# Sheet1.net
KiCad netlist of a schematic drawn in Altium Designer
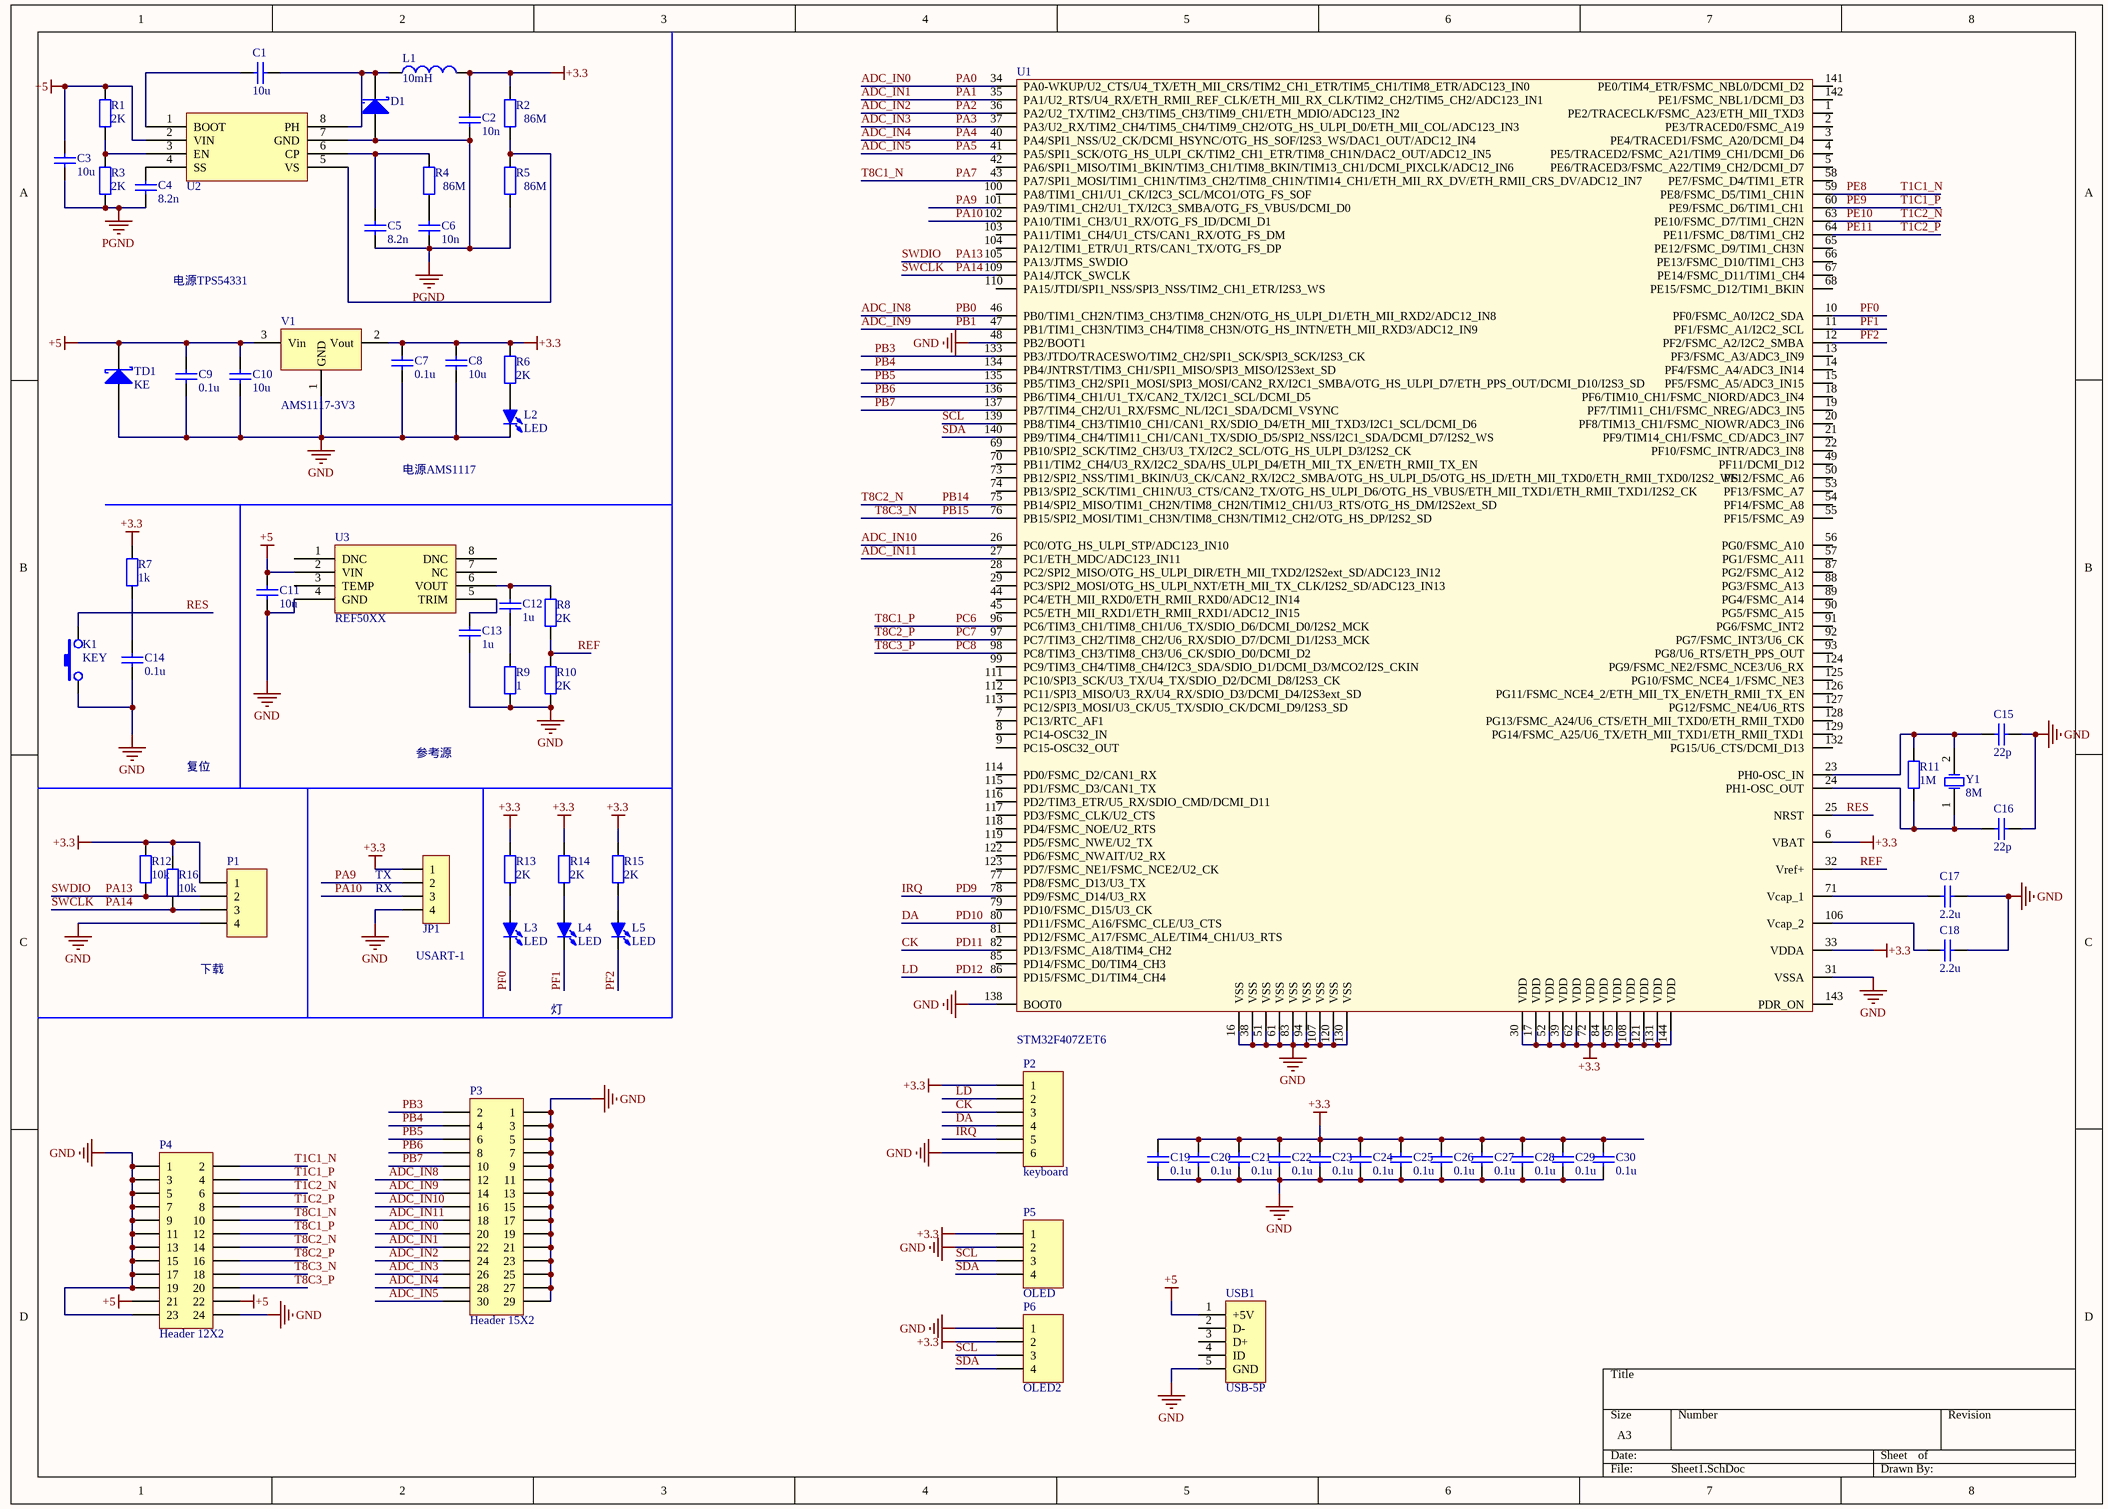
[diagram p0: Sheet1.SchDoc]

(export (version "E")
  (design (tool "Eeschema 10.0.6"))
  (components
    (comp (ref "C1")
      (value "10u")
      (footprint "Miscellaneous Devices:6-0805_N")
      (description "Capacitor")
      (fields (field (name "PUBLISHER") "Altium Limited"))
      (libsource (lib "Miscellaneous Devices") (part "Cap"))
    )
    (comp (ref "C2")
      (value "10n")
      (footprint "Miscellaneous Devices:6-0805_N")
      (description "Capacitor")
      (fields (field (name "PUBLISHER") "Altium Limited"))
      (libsource (lib "Miscellaneous Devices") (part "Cap"))
    )
    (comp (ref "C3")
      (value "10u")
      (footprint "Miscellaneous Devices:6-0805_N")
      (description "Capacitor")
      (fields (field (name "PUBLISHER") "Altium Limited"))
      (libsource (lib "Miscellaneous Devices") (part "Cap"))
    )
    (comp (ref "C4")
      (value "8.2n")
      (footprint "Miscellaneous Devices:6-0805_N")
      (description "Capacitor")
      (fields (field (name "PUBLISHER") "Altium Limited"))
      (libsource (lib "Miscellaneous Devices") (part "Cap"))
    )
    (comp (ref "C5")
      (value "8.2n")
      (footprint "Miscellaneous Devices:6-0805_N")
      (description "Capacitor")
      (fields (field (name "PUBLISHER") "Altium Limited"))
      (libsource (lib "Miscellaneous Devices") (part "Cap"))
    )
    (comp (ref "C6")
      (value "10n")
      (footprint "Miscellaneous Devices:6-0805_N")
      (description "Capacitor")
      (fields (field (name "PUBLISHER") "Altium Limited"))
      (libsource (lib "Miscellaneous Devices") (part "Cap"))
    )
    (comp (ref "C7")
      (value "0.1u")
      (footprint "04 - 电容:C 0603_L")
      (description "Capacitor")
      (fields (field (name "PUBLISHER") "Altium Limited"))
      (libsource (lib "Miscellaneous Devices") (part "Cap"))
    )
    (comp (ref "C8")
      (value "10u")
      (footprint "04 - 电容:C 0805_L")
      (description "Capacitor")
      (fields (field (name "PUBLISHER") "Altium Limited"))
      (libsource (lib "Miscellaneous Devices") (part "Cap"))
    )
    (comp (ref "C9")
      (value "0.1u")
      (footprint "04 - 电容:C 0805_L")
      (description "Capacitor")
      (fields (field (name "PUBLISHER") "Altium Limited"))
      (libsource (lib "Miscellaneous Devices") (part "Cap"))
    )
    (comp (ref "C10")
      (value "10u")
      (footprint "04 - 电容:C 0603_L")
      (description "Capacitor")
      (fields (field (name "PUBLISHER") "Altium Limited"))
      (libsource (lib "Miscellaneous Devices") (part "Cap"))
    )
    (comp (ref "C11")
      (value "10u")
      (footprint "04 - 电容:C 0603_L")
      (description "Capacitor")
      (fields (field (name "PUBLISHER") "Altium Limited"))
      (libsource (lib "Miscellaneous Devices") (part "Cap"))
    )
    (comp (ref "C12")
      (value "1u")
      (footprint "04 - 电容:C 0603_L")
      (description "Capacitor")
      (fields (field (name "PUBLISHER") "Altium Limited"))
      (libsource (lib "Miscellaneous Devices") (part "Cap"))
    )
    (comp (ref "C13")
      (value "1u")
      (footprint "04 - 电容:C 0603_L")
      (description "Capacitor")
      (fields (field (name "PUBLISHER") "Altium Limited"))
      (libsource (lib "Miscellaneous Devices") (part "Cap"))
    )
    (comp (ref "C14")
      (value "0.1u")
      (footprint "04 - 电容:C 0603_L")
      (description "Capacitor")
      (fields (field (name "PUBLISHER") "Altium Limited"))
      (libsource (lib "Miscellaneous Devices") (part "Cap"))
    )
    (comp (ref "C15")
      (value "22p")
      (footprint "04 - 电容:C 0603_L")
      (description "Capacitor")
      (fields (field (name "PUBLISHER") "Altium Limited"))
      (libsource (lib "Miscellaneous Devices") (part "Cap"))
    )
    (comp (ref "C16")
      (value "22p")
      (footprint "04 - 电容:C 0603_L")
      (description "Capacitor")
      (fields (field (name "PUBLISHER") "Altium Limited"))
      (libsource (lib "Miscellaneous Devices") (part "Cap"))
    )
    (comp (ref "C17")
      (value "2.2u")
      (footprint "04 - 电容:C 0805_M")
      (description "Capacitor")
      (fields (field (name "PUBLISHER") "Altium Limited"))
      (libsource (lib "Miscellaneous Devices") (part "Cap"))
    )
    (comp (ref "C18")
      (value "2.2u")
      (footprint "04 - 电容:C 0805_M")
      (description "Capacitor")
      (fields (field (name "PUBLISHER") "Altium Limited"))
      (libsource (lib "Miscellaneous Devices") (part "Cap"))
    )
    (comp (ref "C19")
      (value "0.1u")
      (footprint "04 - 电容:C 0603_L")
      (description "Capacitor")
      (fields (field (name "PUBLISHER") "Altium Limited"))
      (libsource (lib "Miscellaneous Devices") (part "Cap"))
    )
    (comp (ref "C20")
      (value "0.1u")
      (footprint "04 - 电容:C 0603_L")
      (description "Capacitor")
      (fields (field (name "PUBLISHER") "Altium Limited"))
      (libsource (lib "Miscellaneous Devices") (part "Cap"))
    )
    (comp (ref "C21")
      (value "0.1u")
      (footprint "04 - 电容:C 0603_L")
      (description "Capacitor")
      (fields (field (name "PUBLISHER") "Altium Limited"))
      (libsource (lib "Miscellaneous Devices") (part "Cap"))
    )
    (comp (ref "C22")
      (value "0.1u")
      (footprint "04 - 电容:C 0603_L")
      (description "Capacitor")
      (fields (field (name "PUBLISHER") "Altium Limited"))
      (libsource (lib "Miscellaneous Devices") (part "Cap"))
    )
    (comp (ref "C23")
      (value "0.1u")
      (footprint "04 - 电容:C 0603_L")
      (description "Capacitor")
      (fields (field (name "PUBLISHER") "Altium Limited"))
      (libsource (lib "Miscellaneous Devices") (part "Cap"))
    )
    (comp (ref "C24")
      (value "0.1u")
      (footprint "04 - 电容:C 0603_L")
      (description "Capacitor")
      (fields (field (name "PUBLISHER") "Altium Limited"))
      (libsource (lib "Miscellaneous Devices") (part "Cap"))
    )
    (comp (ref "C25")
      (value "0.1u")
      (footprint "04 - 电容:C 0603_L")
      (description "Capacitor")
      (fields (field (name "PUBLISHER") "Altium Limited"))
      (libsource (lib "Miscellaneous Devices") (part "Cap"))
    )
    (comp (ref "C26")
      (value "0.1u")
      (footprint "04 - 电容:C 0603_L")
      (description "Capacitor")
      (fields (field (name "PUBLISHER") "Altium Limited"))
      (libsource (lib "Miscellaneous Devices") (part "Cap"))
    )
    (comp (ref "C27")
      (value "0.1u")
      (footprint "04 - 电容:C 0603_L")
      (description "Capacitor")
      (fields (field (name "PUBLISHER") "Altium Limited"))
      (libsource (lib "Miscellaneous Devices") (part "Cap"))
    )
    (comp (ref "C28")
      (value "0.1u")
      (footprint "04 - 电容:C 0603_L")
      (description "Capacitor")
      (fields (field (name "PUBLISHER") "Altium Limited"))
      (libsource (lib "Miscellaneous Devices") (part "Cap"))
    )
    (comp (ref "C29")
      (value "0.1u")
      (footprint "04 - 电容:C 0603_L")
      (description "Capacitor")
      (fields (field (name "PUBLISHER") "Altium Limited"))
      (libsource (lib "Miscellaneous Devices") (part "Cap"))
    )
    (comp (ref "C30")
      (value "0.1u")
      (footprint "04 - 电容:C 0603_L")
      (description "Capacitor")
      (fields (field (name "PUBLISHER") "Altium Limited"))
      (libsource (lib "Miscellaneous Devices") (part "Cap"))
    )
    (comp (ref "D1")
      (value "D Schottky")
      (footprint "General:SMA")
      (description "Schottky Diode")
      (fields (field (name "PUBLISHER") "Altium Limited"))
      (libsource (lib "Miscellaneous Devices") (part "D Schottky"))
    )
    (comp (ref "JP1")
      (value "HDR-1X4")
      (footprint "XH2.54-WI-4P")
      (description "4P接插件")
      (libsource (lib "18 - 接插件-脚距2.54mm (100mil) ") (part "Header 4"))
    )
    (comp (ref "K1")
      (value "KEY")
      (footprint "KEY-6*6*6")
      (description "四角直插开关")
      (libsource (lib "03 - 按键-开关-晶振-蜂鸣器") (part "KEY"))
    )
    (comp (ref "L1")
      (value "10mH")
      (footprint "05 - 电感:SWPA4030S")
      (description "Inductor")
      (fields (field (name "PUBLISHER") "Altium Limited"))
      (libsource (lib "Miscellaneous Devices") (part "Inductor"))
    )
    (comp (ref "L2")
      (value "LED")
      (footprint "08 - LED发光二极管:LED 0805G")
      (description "发光二极管")
      (libsource (lib "02 - 二极管(LED)-三极管-整流桥") (part "LED"))
    )
    (comp (ref "L3")
      (value "LED")
      (footprint "08 - LED发光二极管:LED 0805G")
      (description "发光二极管")
      (libsource (lib "02 - 二极管(LED)-三极管-整流桥") (part "LED"))
    )
    (comp (ref "L4")
      (value "LED")
      (footprint "08 - LED发光二极管:LED 0805G")
      (description "发光二极管")
      (libsource (lib "02 - 二极管(LED)-三极管-整流桥") (part "LED"))
    )
    (comp (ref "L5")
      (value "LED")
      (footprint "08 - LED发光二极管:LED 0805G")
      (description "发光二极管")
      (libsource (lib "02 - 二极管(LED)-三极管-整流桥") (part "LED"))
    )
    (comp (ref "P1")
      (value "下载")
      (footprint "66 - XH2.54插座:XH2.54-WI-4P")
      (description "Header, 4-Pin")
      (fields (field (name "PUBLISHER") "Altium Limited"))
      (libsource (lib "Miscellaneous Connectors") (part "Header 4"))
    )
    (comp (ref "P2")
      (value "keyboard")
      (footprint "66 - XH2.54插座:XH2.54-WI-6P")
      (description "Header, 6-Pin")
      (fields (field (name "PUBLISHER") "Altium Limited"))
      (libsource (lib "Miscellaneous Connectors") (part "Header 6"))
    )
    (comp (ref "P3")
      (value "Header 15X2")
      (footprint "62 - 排针-排母:HDR2.54-WI-2x15P")
      (description "Header, 15-Pin, Dual row")
      (fields (field (name "PUBLISHER") "Altium Limited"))
      (libsource (lib "Miscellaneous Connectors") (part "Header 15X2"))
    )
    (comp (ref "P4")
      (value "Header 12X2")
      (footprint "62 - 排针-排母:HDR2.54-WI-2x12P")
      (description "Header, 12-Pin, Dual row")
      (fields (field (name "PUBLISHER") "Altium Limited"))
      (libsource (lib "Miscellaneous Connectors") (part "Header 12X2"))
    )
    (comp (ref "P5")
      (value "OLED")
      (footprint "62 - 排针-排母:HDR2.54-M-LI-4P")
      (description "Header, 4-Pin")
      (fields (field (name "PUBLISHER") "Altium Limited"))
      (libsource (lib "Miscellaneous Connectors") (part "Header 4"))
    )
    (comp (ref "P6")
      (value "OLED2")
      (footprint "62 - 排针-排母:HDR2.54-M-LI-4P")
      (description "Header, 4-Pin")
      (fields (field (name "PUBLISHER") "Altium Limited"))
      (libsource (lib "Miscellaneous Connectors") (part "Header 4"))
    )
    (comp (ref "R1")
      (value "2K")
      (footprint "01 - 电阻:R 0603_L")
      (description "Resistor")
      (fields (field (name "PUBLISHER") "Altium Limited"))
      (libsource (lib "Miscellaneous Devices") (part "Res2"))
    )
    (comp (ref "R2")
      (value "86M")
      (footprint "01 - 电阻:R 0603_L")
      (description "Resistor")
      (fields (field (name "PUBLISHER") "Altium Limited"))
      (libsource (lib "Miscellaneous Devices") (part "Res2"))
    )
    (comp (ref "R3")
      (value "2K")
      (footprint "01 - 电阻:R 0603_L")
      (description "Resistor")
      (fields (field (name "PUBLISHER") "Altium Limited"))
      (libsource (lib "Miscellaneous Devices") (part "Res2"))
    )
    (comp (ref "R4")
      (value "86M")
      (footprint "01 - 电阻:R 0603_L")
      (description "Resistor")
      (fields (field (name "PUBLISHER") "Altium Limited"))
      (libsource (lib "Miscellaneous Devices") (part "Res2"))
    )
    (comp (ref "R5")
      (value "86M")
      (footprint "01 - 电阻:R 0603_L")
      (description "Resistor")
      (fields (field (name "PUBLISHER") "Altium Limited"))
      (libsource (lib "Miscellaneous Devices") (part "Res2"))
    )
    (comp (ref "R6")
      (value "2K")
      (footprint "01 - 电阻:R 0603_L")
      (description "Resistor")
      (fields (field (name "PUBLISHER") "Altium Limited"))
      (libsource (lib "Miscellaneous Devices") (part "Res2"))
    )
    (comp (ref "R7")
      (value "1k")
      (footprint "01 - 电阻:R 0603_L")
      (description "Resistor")
      (fields (field (name "PUBLISHER") "Altium Limited"))
      (libsource (lib "Miscellaneous Devices") (part "Res2"))
    )
    (comp (ref "R8")
      (value "2K")
      (footprint "01 - 电阻:R 0603_L")
      (description "Resistor")
      (fields (field (name "PUBLISHER") "Altium Limited"))
      (libsource (lib "Miscellaneous Devices") (part "Res2"))
    )
    (comp (ref "R9")
      (value "1")
      (footprint "01 - 电阻:R 0603_L")
      (description "Resistor")
      (fields (field (name "PUBLISHER") "Altium Limited"))
      (libsource (lib "Miscellaneous Devices") (part "Res2"))
    )
    (comp (ref "R10")
      (value "2K")
      (footprint "01 - 电阻:R 0603_L")
      (description "Resistor")
      (fields (field (name "PUBLISHER") "Altium Limited"))
      (libsource (lib "Miscellaneous Devices") (part "Res2"))
    )
    (comp (ref "R11")
      (value "1M")
      (footprint "01 - 电阻:R 0603_L")
      (description "Resistor")
      (fields (field (name "PUBLISHER") "Altium Limited"))
      (libsource (lib "Miscellaneous Devices") (part "Res2"))
    )
    (comp (ref "R12")
      (value "10k")
      (footprint "01 - 电阻:R 0603_L")
      (description "Resistor")
      (fields (field (name "PUBLISHER") "Altium Limited"))
      (libsource (lib "Miscellaneous Devices") (part "Res2"))
    )
    (comp (ref "R13")
      (value "2K")
      (footprint "01 - 电阻:R 0603_L")
      (description "Resistor")
      (fields (field (name "PUBLISHER") "Altium Limited"))
      (libsource (lib "Miscellaneous Devices") (part "Res2"))
    )
    (comp (ref "R14")
      (value "2K")
      (footprint "01 - 电阻:R 0603_L")
      (description "Resistor")
      (fields (field (name "PUBLISHER") "Altium Limited"))
      (libsource (lib "Miscellaneous Devices") (part "Res2"))
    )
    (comp (ref "R15")
      (value "2K")
      (footprint "01 - 电阻:R 0603_L")
      (description "Resistor")
      (fields (field (name "PUBLISHER") "Altium Limited"))
      (libsource (lib "Miscellaneous Devices") (part "Res2"))
    )
    (comp (ref "R16")
      (value "10k")
      (footprint "01 - 电阻:R 0603_L")
      (description "Resistor")
      (fields (field (name "PUBLISHER") "Altium Limited"))
      (libsource (lib "Miscellaneous Devices") (part "Res2"))
    )
    (comp (ref "TD1")
      (value "KE")
      (footprint "07 - 二极管-整流桥堆:SMB")
      (description "Schottky Diode")
      (fields (field (name "PUBLISHER") "Altium Limited"))
      (libsource (lib "Miscellaneous Devices") (part "D Schottky"))
    )
    (comp (ref "U1")
      (value "STM32F407ZET6")
      (footprint "LQFP144")
      (libsource (lib "Explorer STM32F407封装库") (part "STM32F407ZET6"))
    )
    (comp (ref "U2")
      (value "TPS54331")
      (footprint "my:tps5450")
      (description "28V输入 3A")
      (libsource (lib "my") (part "TPS54331"))
    )
    (comp (ref "U3")
      (value "REF50XX")
      (footprint "11 - SO封装:SO-8")
      (description "基准源")
      (libsource (lib "my") (part "REF50XX"))
    )
    (comp (ref "USB1")
      (value "USB-5P")
      (footprint "48 - USB micro、3.1 Type C接口:USB-micro_A")
      (description "微型USB母座")
      (libsource (lib "04 - 接口类-USB接口-网口") (part "USB-5P"))
    )
    (comp (ref "V1")
      (value "AMS1117-3V3")
      (footprint "SOT223_N")
      (description "三端稳压芯片")
      (libsource (lib "08 - 稳压芯片-电源管理芯片") (part "AMS1117"))
    )
    (comp (ref "Y1")
      (value "8M")
      (footprint "09 - 晶振-晶体:OSC HC-49SMD")
      (description "Crystal Oscillator")
      (fields (field (name "PUBLISHER") "Altium Limited"))
      (libsource (lib "Miscellaneous Devices") (part "XTAL"))
    )
  )
  (nets
    (net (code "1") (name "+3.3") (class "Default")
      (node (ref "C19") (pin "2") (pinfunction "2_2") (pintype "passive"))
      (node (ref "C2") (pin "1") (pinfunction "1_1") (pintype "passive"))
      (node (ref "C20") (pin "2") (pinfunction "2_2") (pintype "passive"))
      (node (ref "C21") (pin "2") (pinfunction "2_2") (pintype "passive"))
      (node (ref "C22") (pin "2") (pinfunction "2_2") (pintype "passive"))
      (node (ref "C23") (pin "2") (pinfunction "2_2") (pintype "passive"))
      (node (ref "C24") (pin "2") (pinfunction "2_2") (pintype "passive"))
      (node (ref "C25") (pin "2") (pinfunction "2_2") (pintype "passive"))
      (node (ref "C26") (pin "2") (pinfunction "2_2") (pintype "passive"))
      (node (ref "C27") (pin "2") (pinfunction "2_2") (pintype "passive"))
      (node (ref "C28") (pin "2") (pinfunction "2_2") (pintype "passive"))
      (node (ref "C29") (pin "2") (pinfunction "2_2") (pintype "passive"))
      (node (ref "C30") (pin "2") (pinfunction "2_2") (pintype "passive"))
      (node (ref "C7") (pin "2") (pinfunction "2_2") (pintype "passive"))
      (node (ref "C8") (pin "2") (pinfunction "2_2") (pintype "passive"))
      (node (ref "JP1") (pin "1") (pinfunction "1_1") (pintype "passive"))
      (node (ref "L1") (pin "2") (pinfunction "2_2") (pintype "passive"))
      (node (ref "P1") (pin "1") (pinfunction "1_1") (pintype "passive"))
      (node (ref "P2") (pin "1") (pinfunction "1_1") (pintype "passive"))
      (node (ref "P5") (pin "1") (pinfunction "1_1") (pintype "passive"))
      (node (ref "P6") (pin "2") (pinfunction "2_2") (pintype "passive"))
      (node (ref "R12") (pin "2") (pinfunction "2_2") (pintype "passive"))
      (node (ref "R13") (pin "2") (pinfunction "2_2") (pintype "passive"))
      (node (ref "R14") (pin "2") (pinfunction "2_2") (pintype "passive"))
      (node (ref "R15") (pin "2") (pinfunction "2_2") (pintype "passive"))
      (node (ref "R16") (pin "2") (pinfunction "2_2") (pintype "passive"))
      (node (ref "R2") (pin "2") (pinfunction "2_2") (pintype "passive"))
      (node (ref "R6") (pin "2") (pinfunction "2_2") (pintype "passive"))
      (node (ref "R7") (pin "2") (pinfunction "2_2") (pintype "passive"))
      (node (ref "U1") (pin "108") (pinfunction "VDD_108") (pintype "passive"))
      (node (ref "U1") (pin "121") (pinfunction "VDD_121") (pintype "passive"))
      (node (ref "U1") (pin "131") (pinfunction "VDD_131") (pintype "passive"))
      (node (ref "U1") (pin "144") (pinfunction "VDD_144") (pintype "passive"))
      (node (ref "U1") (pin "17") (pinfunction "VDD_17") (pintype "passive"))
      (node (ref "U1") (pin "30") (pinfunction "VDD_30") (pintype "passive"))
      (node (ref "U1") (pin "33") (pinfunction "VDDA_33") (pintype "passive"))
      (node (ref "U1") (pin "39") (pinfunction "VDD_39") (pintype "passive"))
      (node (ref "U1") (pin "52") (pinfunction "VDD_52") (pintype "passive"))
      (node (ref "U1") (pin "6") (pinfunction "VBAT_6") (pintype "passive"))
      (node (ref "U1") (pin "62") (pinfunction "VDD_62") (pintype "passive"))
      (node (ref "U1") (pin "72") (pinfunction "VDD_72") (pintype "passive"))
      (node (ref "U1") (pin "84") (pinfunction "VDD_84") (pintype "passive"))
      (node (ref "U1") (pin "95") (pinfunction "VDD_95") (pintype "passive"))
      (node (ref "V1") (pin "2") (pinfunction "Vout_2") (pintype "passive"))
    )
    (net (code "2") (name "+5") (class "Default")
      (node (ref "C10") (pin "2") (pinfunction "2_2") (pintype "passive"))
      (node (ref "C11") (pin "2") (pinfunction "2_2") (pintype "passive"))
      (node (ref "C3") (pin "1") (pinfunction "1_1") (pintype "passive"))
      (node (ref "C9") (pin "2") (pinfunction "2_2") (pintype "passive"))
      (node (ref "P4") (pin "21") (pinfunction "21_21") (pintype "passive"))
      (node (ref "P4") (pin "22") (pinfunction "22_22") (pintype "passive"))
      (node (ref "R1") (pin "2") (pinfunction "2_2") (pintype "passive"))
      (node (ref "TD1") (pin "2") (pinfunction "K_2") (pintype "passive"))
      (node (ref "U2") (pin "2") (pinfunction "VIN_2") (pintype "passive"))
      (node (ref "U3") (pin "2") (pinfunction "VIN_2") (pintype "passive"))
      (node (ref "USB1") (pin "1") (pinfunction "+5V_1") (pintype "passive"))
      (node (ref "V1") (pin "3") (pinfunction "Vin_3") (pintype "passive"))
    )
    (net (code "3") (name "/ADC_IN0") (class "Default")
      (node (ref "P3") (pin "20") (pinfunction "20_20") (pintype "passive"))
      (node (ref "U1") (pin "34") (pinfunction "PA0-WKUP/U2_CTS/U4_TX/ETH_MII_CRS/TIM2_CH1_ETR/TIM5_CH1/TIM8_ETR/ADC123_IN0_34") (pintype "passive"))
    )
    (net (code "4") (name "/ADC_IN1") (class "Default")
      (node (ref "P3") (pin "22") (pinfunction "22_22") (pintype "passive"))
      (node (ref "U1") (pin "35") (pinfunction "PA1/U2_RTS/U4_RX/ETH_RMII_REF_CLK/ETH_MII_RX_CLK/TIM2_CH2/TIM5_CH2/ADC123_IN1_35") (pintype "passive"))
    )
    (net (code "5") (name "/ADC_IN2") (class "Default")
      (node (ref "P3") (pin "24") (pinfunction "24_24") (pintype "passive"))
      (node (ref "U1") (pin "36") (pinfunction "PA2/U2_TX/TIM2_CH3/TIM5_CH3/TIM9_CH1/ETH_MDIO/ADC123_IN2_36") (pintype "passive"))
    )
    (net (code "6") (name "/ADC_IN3") (class "Default")
      (node (ref "P3") (pin "26") (pinfunction "26_26") (pintype "passive"))
      (node (ref "U1") (pin "37") (pinfunction "PA3/U2_RX/TIM2_CH4/TIM5_CH4/TIM9_CH2/OTG_HS_ULPI_D0/ETH_MII_COL/ADC123_IN3_37") (pintype "passive"))
    )
    (net (code "7") (name "/ADC_IN4") (class "Default")
      (node (ref "P3") (pin "28") (pinfunction "28_28") (pintype "passive"))
      (node (ref "U1") (pin "40") (pinfunction "PA4/SPI1_NSS/U2_CK/DCMI_HSYNC/OTG_HS_SOF/I2S3_WS/DAC1_OUT/ADC12_IN4_40") (pintype "passive"))
    )
    (net (code "8") (name "/ADC_IN5") (class "Default")
      (node (ref "P3") (pin "30") (pinfunction "30_30") (pintype "passive"))
      (node (ref "U1") (pin "41") (pinfunction "PA5/SPI1_SCK/OTG_HS_ULPI_CK/TIM2_CH1_ETR/TIM8_CH1N/DAC2_OUT/ADC12_IN5_41") (pintype "passive"))
    )
    (net (code "9") (name "/ADC_IN8") (class "Default")
      (node (ref "P3") (pin "12") (pinfunction "12_12") (pintype "passive"))
      (node (ref "U1") (pin "46") (pinfunction "PB0/TIM1_CH2N/TIM3_CH3/TIM8_CH2N/OTG_HS_ULPI_D1/ETH_MII_RXD2/ADC12_IN8_46") (pintype "passive"))
    )
    (net (code "10") (name "/ADC_IN9") (class "Default")
      (node (ref "P3") (pin "14") (pinfunction "14_14") (pintype "passive"))
      (node (ref "U1") (pin "47") (pinfunction "PB1/TIM1_CH3N/TIM3_CH4/TIM8_CH3N/OTG_HS_INTN/ETH_MII_RXD3/ADC12_IN9_47") (pintype "passive"))
    )
    (net (code "11") (name "/ADC_IN10") (class "Default")
      (node (ref "P3") (pin "16") (pinfunction "16_16") (pintype "passive"))
      (node (ref "U1") (pin "26") (pinfunction "PC0/OTG_HS_ULPI_STP/ADC123_IN10_26") (pintype "passive"))
    )
    (net (code "12") (name "/ADC_IN11") (class "Default")
      (node (ref "P3") (pin "18") (pinfunction "18_18") (pintype "passive"))
      (node (ref "U1") (pin "27") (pinfunction "PC1/ETH_MDC/ADC123_IN11_27") (pintype "passive"))
    )
    (net (code "13") (name "/CK") (class "Default")
      (node (ref "P2") (pin "3") (pinfunction "3_3") (pintype "passive"))
      (node (ref "U1") (pin "82") (pinfunction "PD13/FSMC_A18/TIM4_CH2_82") (pintype "passive"))
    )
    (net (code "14") (name "/DA") (class "Default")
      (node (ref "P2") (pin "4") (pinfunction "4_4") (pintype "passive"))
      (node (ref "U1") (pin "80") (pinfunction "PD11/FSMC_A16/FSMC_CLE/U3_CTS_80") (pintype "passive"))
    )
    (net (code "15") (name "/IRQ") (class "Default")
      (node (ref "P2") (pin "5") (pinfunction "5_5") (pintype "passive"))
      (node (ref "U1") (pin "78") (pinfunction "PD9/FSMC_D14/U3_RX_78") (pintype "passive"))
    )
    (net (code "16") (name "/LD") (class "Default")
      (node (ref "P2") (pin "2") (pinfunction "2_2") (pintype "passive"))
      (node (ref "U1") (pin "86") (pinfunction "PD15/FSMC_D1/TIM4_CH4_86") (pintype "passive"))
    )
    (net (code "17") (name "/PA7") (class "Default")
      (node (ref "P4") (pin "10") (pinfunction "10_10") (pintype "passive"))
      (node (ref "U1") (pin "43") (pinfunction "PA7/SPI1_MOSI/TIM1_CH1N/TIM3_CH2/TIM8_CH1N/TIM14_CH1/ETH_MII_RX_DV/ETH_RMII_CRS_DV/ADC12_IN7_43") (pintype "passive"))
    )
    (net (code "18") (name "/PA9") (class "Default")
      (node (ref "JP1") (pin "2") (pinfunction "2_2") (pintype "passive"))
      (node (ref "U1") (pin "101") (pinfunction "PA9/TIM1_CH2/U1_TX/I2C3_SMBA/OTG_FS_VBUS/DCMI_D0_101") (pintype "passive"))
    )
    (net (code "19") (name "/PA10") (class "Default")
      (node (ref "JP1") (pin "3") (pinfunction "3_3") (pintype "passive"))
      (node (ref "U1") (pin "102") (pinfunction "PA10/TIM1_CH3/U1_RX/OTG_FS_ID/DCMI_D1_102") (pintype "passive"))
    )
    (net (code "20") (name "/PA13") (class "Default")
      (node (ref "P1") (pin "2") (pinfunction "2_2") (pintype "passive"))
      (node (ref "R12") (pin "1") (pinfunction "1_1") (pintype "passive"))
      (node (ref "U1") (pin "105") (pinfunction "PA13/JTMS_SWDIO_105") (pintype "passive"))
    )
    (net (code "21") (name "/PA14") (class "Default")
      (node (ref "P1") (pin "3") (pinfunction "3_3") (pintype "passive"))
      (node (ref "R16") (pin "1") (pinfunction "1_1") (pintype "passive"))
      (node (ref "U1") (pin "109") (pinfunction "PA14/JTCK_SWCLK_109") (pintype "passive"))
    )
    (net (code "22") (name "/PB3") (class "Default")
      (node (ref "P3") (pin "2") (pinfunction "2_2") (pintype "passive"))
      (node (ref "U1") (pin "133") (pinfunction "PB3/JTDO/TRACESWO/TIM2_CH2/SPI1_SCK/SPI3_SCK/I2S3_CK_133") (pintype "passive"))
    )
    (net (code "23") (name "/PB4") (class "Default")
      (node (ref "P3") (pin "4") (pinfunction "4_4") (pintype "passive"))
      (node (ref "U1") (pin "134") (pinfunction "PB4/JNTRST/TIM3_CH1/SPI1_MISO/SPI3_MISO/I2S3ext_SD_134") (pintype "passive"))
    )
    (net (code "24") (name "/PB5") (class "Default")
      (node (ref "P3") (pin "6") (pinfunction "6_6") (pintype "passive"))
      (node (ref "U1") (pin "135") (pinfunction "PB5/TIM3_CH2/SPI1_MOSI/SPI3_MOSI/CAN2_RX/I2C1_SMBA/OTG_HS_ULPI_D7/ETH_PPS_OUT/DCMI_D10/I2S3_SD_135") (pintype "passive"))
    )
    (net (code "25") (name "/PB6") (class "Default")
      (node (ref "P3") (pin "8") (pinfunction "8_8") (pintype "passive"))
      (node (ref "U1") (pin "136") (pinfunction "PB6/TIM4_CH1/U1_TX/CAN2_TX/I2C1_SCL/DCMI_D5_136") (pintype "passive"))
    )
    (net (code "26") (name "/PB7") (class "Default")
      (node (ref "P3") (pin "10") (pinfunction "10_10") (pintype "passive"))
      (node (ref "U1") (pin "137") (pinfunction "PB7/TIM4_CH2/U1_RX/FSMC_NL/I2C1_SDA/DCMI_VSYNC_137") (pintype "passive"))
    )
    (net (code "27") (name "/PB14") (class "Default")
      (node (ref "P4") (pin "14") (pinfunction "14_14") (pintype "passive"))
      (node (ref "U1") (pin "75") (pinfunction "PB14/SPI2_MISO/TIM1_CH2N/TIM8_CH2N/TIM12_CH1/U3_RTS/OTG_HS_DM/I2S2ext_SD_75") (pintype "passive"))
    )
    (net (code "28") (name "/PB15") (class "Default")
      (node (ref "P4") (pin "18") (pinfunction "18_18") (pintype "passive"))
      (node (ref "U1") (pin "76") (pinfunction "PB15/SPI2_MOSI/TIM1_CH3N/TIM8_CH3N/TIM12_CH2/OTG_HS_DP/I2S2_SD_76") (pintype "passive"))
    )
    (net (code "29") (name "/PC6") (class "Default")
      (node (ref "P4") (pin "12") (pinfunction "12_12") (pintype "passive"))
      (node (ref "U1") (pin "96") (pinfunction "PC6/TIM3_CH1/TIM8_CH1/U6_TX/SDIO_D6/DCMI_D0/I2S2_MCK_96") (pintype "passive"))
    )
    (net (code "30") (name "/PC7") (class "Default")
      (node (ref "P4") (pin "16") (pinfunction "16_16") (pintype "passive"))
      (node (ref "U1") (pin "97") (pinfunction "PC7/TIM3_CH2/TIM8_CH2/U6_RX/SDIO_D7/DCMI_D1/I2S3_MCK_97") (pintype "passive"))
    )
    (net (code "31") (name "/PC8") (class "Default")
      (node (ref "P4") (pin "20") (pinfunction "20_20") (pintype "passive"))
      (node (ref "U1") (pin "98") (pinfunction "PC8/TIM3_CH3/TIM8_CH3/U6_CK/SDIO_D0/DCMI_D2_98") (pintype "passive"))
    )
    (net (code "32") (name "/PE8") (class "Default")
      (node (ref "P4") (pin "2") (pinfunction "2_2") (pintype "passive"))
      (node (ref "U1") (pin "59") (pinfunction "PE8/FSMC_D5/TIM1_CH1N_59") (pintype "passive"))
    )
    (net (code "33") (name "/PE9") (class "Default")
      (node (ref "P4") (pin "4") (pinfunction "4_4") (pintype "passive"))
      (node (ref "U1") (pin "60") (pinfunction "PE9/FSMC_D6/TIM1_CH1_60") (pintype "passive"))
    )
    (net (code "34") (name "/PE10") (class "Default")
      (node (ref "P4") (pin "6") (pinfunction "6_6") (pintype "passive"))
      (node (ref "U1") (pin "63") (pinfunction "PE10/FSMC_D7/TIM1_CH2N_63") (pintype "passive"))
    )
    (net (code "35") (name "/PE11") (class "Default")
      (node (ref "P4") (pin "8") (pinfunction "8_8") (pintype "passive"))
      (node (ref "U1") (pin "64") (pinfunction "PE11/FSMC_D8/TIM1_CH2_64") (pintype "passive"))
    )
    (net (code "36") (name "/PF0") (class "Default")
      (node (ref "L3") (pin "2") (pinfunction "K_2") (pintype "passive"))
      (node (ref "U1") (pin "10") (pinfunction "PF0/FSMC_A0/I2C2_SDA_10") (pintype "passive"))
    )
    (net (code "37") (name "/PF1") (class "Default")
      (node (ref "L4") (pin "2") (pinfunction "K_2") (pintype "passive"))
      (node (ref "U1") (pin "11") (pinfunction "PF1/FSMC_A1/I2C2_SCL_11") (pintype "passive"))
    )
    (net (code "38") (name "/PF2") (class "Default")
      (node (ref "L5") (pin "2") (pinfunction "K_2") (pintype "passive"))
      (node (ref "U1") (pin "12") (pinfunction "PF2/FSMC_A2/I2C2_SMBA_12") (pintype "passive"))
    )
    (net (code "39") (name "/REF") (class "Default")
      (node (ref "R10") (pin "2") (pinfunction "2_2") (pintype "passive"))
      (node (ref "R8") (pin "1") (pinfunction "1_1") (pintype "passive"))
      (node (ref "U1") (pin "32") (pinfunction "Vref+_32") (pintype "passive"))
    )
    (net (code "40") (name "/RES") (class "Default")
      (node (ref "K1") (pin "2") (pinfunction "2_2") (pintype "passive"))
      (node (ref "U1") (pin "25") (pinfunction "NRST_25") (pintype "passive"))
    )
    (net (code "41") (name "/SCL") (class "Default")
      (node (ref "P5") (pin "3") (pinfunction "3_3") (pintype "passive"))
      (node (ref "P6") (pin "3") (pinfunction "3_3") (pintype "passive"))
      (node (ref "U1") (pin "139") (pinfunction "PB8/TIM4_CH3/TIM10_CH1/CAN1_RX/SDIO_D4/ETH_MII_TXD3/I2C1_SCL/DCMI_D6_139") (pintype "passive"))
    )
    (net (code "42") (name "/SDA") (class "Default")
      (node (ref "P5") (pin "4") (pinfunction "4_4") (pintype "passive"))
      (node (ref "P6") (pin "4") (pinfunction "4_4") (pintype "passive"))
      (node (ref "U1") (pin "140") (pinfunction "PB9/TIM4_CH4/TIM11_CH1/CAN1_TX/SDIO_D5/SPI2_NSS/I2C1_SDA/DCMI_D7/I2S2_WS_140") (pintype "passive"))
    )
    (net (code "43") (name "GND") (class "Default")
      (node (ref "C10") (pin "1") (pinfunction "1_1") (pintype "passive"))
      (node (ref "C11") (pin "1") (pinfunction "1_1") (pintype "passive"))
      (node (ref "C13") (pin "1") (pinfunction "1_1") (pintype "passive"))
      (node (ref "C14") (pin "1") (pinfunction "1_1") (pintype "passive"))
      (node (ref "C15") (pin "2") (pinfunction "2_2") (pintype "passive"))
      (node (ref "C16") (pin "2") (pinfunction "2_2") (pintype "passive"))
      (node (ref "C17") (pin "2") (pinfunction "2_2") (pintype "passive"))
      (node (ref "C18") (pin "2") (pinfunction "2_2") (pintype "passive"))
      (node (ref "C19") (pin "1") (pinfunction "1_1") (pintype "passive"))
      (node (ref "C20") (pin "1") (pinfunction "1_1") (pintype "passive"))
      (node (ref "C21") (pin "1") (pinfunction "1_1") (pintype "passive"))
      (node (ref "C22") (pin "1") (pinfunction "1_1") (pintype "passive"))
      (node (ref "C23") (pin "1") (pinfunction "1_1") (pintype "passive"))
      (node (ref "C24") (pin "1") (pinfunction "1_1") (pintype "passive"))
      (node (ref "C25") (pin "1") (pinfunction "1_1") (pintype "passive"))
      (node (ref "C26") (pin "1") (pinfunction "1_1") (pintype "passive"))
      (node (ref "C27") (pin "1") (pinfunction "1_1") (pintype "passive"))
      (node (ref "C28") (pin "1") (pinfunction "1_1") (pintype "passive"))
      (node (ref "C29") (pin "1") (pinfunction "1_1") (pintype "passive"))
      (node (ref "C30") (pin "1") (pinfunction "1_1") (pintype "passive"))
      (node (ref "C7") (pin "1") (pinfunction "1_1") (pintype "passive"))
      (node (ref "C8") (pin "1") (pinfunction "1_1") (pintype "passive"))
      (node (ref "C9") (pin "1") (pinfunction "1_1") (pintype "passive"))
      (node (ref "JP1") (pin "4") (pinfunction "4_4") (pintype "passive"))
      (node (ref "K1") (pin "1") (pinfunction "1_1") (pintype "passive"))
      (node (ref "L2") (pin "2") (pinfunction "K_2") (pintype "passive"))
      (node (ref "P1") (pin "4") (pinfunction "4_4") (pintype "passive"))
      (node (ref "P2") (pin "6") (pinfunction "6_6") (pintype "passive"))
      (node (ref "P3") (pin "1") (pinfunction "1_1") (pintype "passive"))
      (node (ref "P3") (pin "11") (pinfunction "11_11") (pintype "passive"))
      (node (ref "P3") (pin "13") (pinfunction "13_13") (pintype "passive"))
      (node (ref "P3") (pin "15") (pinfunction "15_15") (pintype "passive"))
      (node (ref "P3") (pin "17") (pinfunction "17_17") (pintype "passive"))
      (node (ref "P3") (pin "19") (pinfunction "19_19") (pintype "passive"))
      (node (ref "P3") (pin "21") (pinfunction "21_21") (pintype "passive"))
      (node (ref "P3") (pin "23") (pinfunction "23_23") (pintype "passive"))
      (node (ref "P3") (pin "25") (pinfunction "25_25") (pintype "passive"))
      (node (ref "P3") (pin "27") (pinfunction "27_27") (pintype "passive"))
      (node (ref "P3") (pin "29") (pinfunction "29_29") (pintype "passive"))
      (node (ref "P3") (pin "3") (pinfunction "3_3") (pintype "passive"))
      (node (ref "P3") (pin "5") (pinfunction "5_5") (pintype "passive"))
      (node (ref "P3") (pin "7") (pinfunction "7_7") (pintype "passive"))
      (node (ref "P3") (pin "9") (pinfunction "9_9") (pintype "passive"))
      (node (ref "P4") (pin "1") (pinfunction "1_1") (pintype "passive"))
      (node (ref "P4") (pin "11") (pinfunction "11_11") (pintype "passive"))
      (node (ref "P4") (pin "13") (pinfunction "13_13") (pintype "passive"))
      (node (ref "P4") (pin "15") (pinfunction "15_15") (pintype "passive"))
      (node (ref "P4") (pin "17") (pinfunction "17_17") (pintype "passive"))
      (node (ref "P4") (pin "19") (pinfunction "19_19") (pintype "passive"))
      (node (ref "P4") (pin "23") (pinfunction "23_23") (pintype "passive"))
      (node (ref "P4") (pin "24") (pinfunction "24_24") (pintype "passive"))
      (node (ref "P4") (pin "3") (pinfunction "3_3") (pintype "passive"))
      (node (ref "P4") (pin "5") (pinfunction "5_5") (pintype "passive"))
      (node (ref "P4") (pin "7") (pinfunction "7_7") (pintype "passive"))
      (node (ref "P4") (pin "9") (pinfunction "9_9") (pintype "passive"))
      (node (ref "P5") (pin "2") (pinfunction "2_2") (pintype "passive"))
      (node (ref "P6") (pin "1") (pinfunction "1_1") (pintype "passive"))
      (node (ref "R10") (pin "1") (pinfunction "1_1") (pintype "passive"))
      (node (ref "R9") (pin "1") (pinfunction "1_1") (pintype "passive"))
      (node (ref "TD1") (pin "1") (pinfunction "A_1") (pintype "passive"))
      (node (ref "U1") (pin "107") (pinfunction "VSS_107") (pintype "passive"))
      (node (ref "U1") (pin "120") (pinfunction "VSS_120") (pintype "passive"))
      (node (ref "U1") (pin "130") (pinfunction "VSS_130") (pintype "passive"))
      (node (ref "U1") (pin "138") (pinfunction "BOOT0_138") (pintype "passive"))
      (node (ref "U1") (pin "16") (pinfunction "VSS_16") (pintype "passive"))
      (node (ref "U1") (pin "31") (pinfunction "VSSA_31") (pintype "passive"))
      (node (ref "U1") (pin "38") (pinfunction "VSS_38") (pintype "passive"))
      (node (ref "U1") (pin "48") (pinfunction "PB2/BOOT1_48") (pintype "passive"))
      (node (ref "U1") (pin "51") (pinfunction "VSS_51") (pintype "passive"))
      (node (ref "U1") (pin "61") (pinfunction "VSS_61") (pintype "passive"))
      (node (ref "U1") (pin "83") (pinfunction "VSS_83") (pintype "passive"))
      (node (ref "U1") (pin "94") (pinfunction "VSS_94") (pintype "passive"))
      (node (ref "U3") (pin "4") (pinfunction "GND_4") (pintype "passive"))
      (node (ref "USB1") (pin "5") (pinfunction "GND_5") (pintype "passive"))
      (node (ref "V1") (pin "1") (pinfunction "GND_1") (pintype "passive"))
    )
    (net (code "44") (name "Net-(C6-Pad1)") (class "Default")
      (node (ref "C6") (pin "1") (pinfunction "1_1") (pintype "passive"))
      (node (ref "R4") (pin "1") (pinfunction "1_1") (pintype "passive"))
    )
    (net (code "45") (name "Net-(C12-Pad1)") (class "Default")
      (node (ref "C12") (pin "1") (pinfunction "1_1") (pintype "passive"))
      (node (ref "R9") (pin "2") (pinfunction "2_2") (pintype "passive"))
    )
    (net (code "46") (name "Net-(C14-Pad2)") (class "Default")
      (node (ref "C14") (pin "2") (pinfunction "2_2") (pintype "passive"))
      (node (ref "R7") (pin "1") (pinfunction "1_1") (pintype "passive"))
    )
    (net (code "47") (name "Net-(D1-K)") (class "Default")
      (node (ref "C1") (pin "1") (pinfunction "1_1") (pintype "passive"))
      (node (ref "D1") (pin "2") (pinfunction "K_2") (pintype "passive"))
      (node (ref "L1") (pin "1") (pinfunction "1_1") (pintype "passive"))
      (node (ref "U2") (pin "8") (pinfunction "PH_8") (pintype "passive"))
    )
    (net (code "48") (name "Net-(L2-A)") (class "Default")
      (node (ref "L2") (pin "1") (pinfunction "A_1") (pintype "passive"))
      (node (ref "R6") (pin "1") (pinfunction "1_1") (pintype "passive"))
    )
    (net (code "49") (name "Net-(L3-A)") (class "Default")
      (node (ref "L3") (pin "1") (pinfunction "A_1") (pintype "passive"))
      (node (ref "R13") (pin "1") (pinfunction "1_1") (pintype "passive"))
    )
    (net (code "50") (name "Net-(L4-A)") (class "Default")
      (node (ref "L4") (pin "1") (pinfunction "A_1") (pintype "passive"))
      (node (ref "R14") (pin "1") (pinfunction "1_1") (pintype "passive"))
    )
    (net (code "51") (name "Net-(L5-A)") (class "Default")
      (node (ref "L5") (pin "1") (pinfunction "A_1") (pintype "passive"))
      (node (ref "R15") (pin "1") (pinfunction "1_1") (pintype "passive"))
    )
    (net (code "52") (name "Net-(U1-PH0-OSC_IN)") (class "Default")
      (node (ref "C15") (pin "1") (pinfunction "1_1") (pintype "passive"))
      (node (ref "R11") (pin "2") (pinfunction "2_2") (pintype "passive"))
      (node (ref "U1") (pin "23") (pinfunction "PH0-OSC_IN_23") (pintype "passive"))
      (node (ref "Y1") (pin "2") (pinfunction "OSC2_2") (pintype "passive"))
    )
    (net (code "53") (name "Net-(U1-PH1-OSC_OUT)") (class "Default")
      (node (ref "C16") (pin "1") (pinfunction "1_1") (pintype "passive"))
      (node (ref "R11") (pin "1") (pinfunction "1_1") (pintype "passive"))
      (node (ref "U1") (pin "24") (pinfunction "PH1-OSC_OUT_24") (pintype "passive"))
      (node (ref "Y1") (pin "1") (pinfunction "OSC1_1") (pintype "passive"))
    )
    (net (code "54") (name "Net-(U1-Vcap_1)") (class "Default")
      (node (ref "C17") (pin "1") (pinfunction "1_1") (pintype "passive"))
      (node (ref "U1") (pin "71") (pinfunction "Vcap_1_71") (pintype "passive"))
    )
    (net (code "55") (name "Net-(U1-Vcap_2)") (class "Default")
      (node (ref "C18") (pin "1") (pinfunction "1_1") (pintype "passive"))
      (node (ref "U1") (pin "106") (pinfunction "Vcap_2_106") (pintype "passive"))
    )
    (net (code "56") (name "Net-(U2-BOOT)") (class "Default")
      (node (ref "C1") (pin "2") (pinfunction "2_2") (pintype "passive"))
      (node (ref "U2") (pin "1") (pinfunction "BOOT_1") (pintype "passive"))
    )
    (net (code "57") (name "Net-(U2-CP)") (class "Default")
      (node (ref "C5") (pin "1") (pinfunction "1_1") (pintype "passive"))
      (node (ref "R4") (pin "2") (pinfunction "2_2") (pintype "passive"))
      (node (ref "U2") (pin "6") (pinfunction "CP_6") (pintype "passive"))
    )
    (net (code "58") (name "Net-(U2-EN)") (class "Default")
      (node (ref "R1") (pin "1") (pinfunction "1_1") (pintype "passive"))
      (node (ref "R3") (pin "2") (pinfunction "2_2") (pintype "passive"))
      (node (ref "U2") (pin "3") (pinfunction "EN_3") (pintype "passive"))
    )
    (net (code "59") (name "Net-(U2-SS)") (class "Default")
      (node (ref "C4") (pin "1") (pinfunction "1_1") (pintype "passive"))
      (node (ref "U2") (pin "4") (pinfunction "SS_4") (pintype "passive"))
    )
    (net (code "60") (name "Net-(U2-VS)") (class "Default")
      (node (ref "R2") (pin "1") (pinfunction "1_1") (pintype "passive"))
      (node (ref "R5") (pin "2") (pinfunction "2_2") (pintype "passive"))
      (node (ref "U2") (pin "5") (pinfunction "VS_5") (pintype "passive"))
    )
    (net (code "61") (name "Net-(U3-TRIM)") (class "Default")
      (node (ref "C13") (pin "2") (pinfunction "2_2") (pintype "passive"))
      (node (ref "U3") (pin "5") (pinfunction "TRIM_5") (pintype "passive"))
    )
    (net (code "62") (name "Net-(U3-VOUT)") (class "Default")
      (node (ref "C12") (pin "2") (pinfunction "2_2") (pintype "passive"))
      (node (ref "R8") (pin "2") (pinfunction "2_2") (pintype "passive"))
      (node (ref "U3") (pin "6") (pinfunction "VOUT_6") (pintype "passive"))
    )
    (net (code "63") (name "PGND") (class "Default")
      (node (ref "C2") (pin "2") (pinfunction "2_2") (pintype "passive"))
      (node (ref "C3") (pin "2") (pinfunction "2_2") (pintype "passive"))
      (node (ref "C4") (pin "2") (pinfunction "2_2") (pintype "passive"))
      (node (ref "C5") (pin "2") (pinfunction "2_2") (pintype "passive"))
      (node (ref "C6") (pin "2") (pinfunction "2_2") (pintype "passive"))
      (node (ref "D1") (pin "1") (pinfunction "A_1") (pintype "passive"))
      (node (ref "R3") (pin "1") (pinfunction "1_1") (pintype "passive"))
      (node (ref "R5") (pin "1") (pinfunction "1_1") (pintype "passive"))
      (node (ref "U2") (pin "7") (pinfunction "GND_7") (pintype "passive"))
    )
    (net (code "64") (name "unconnected-(U1-PA6{slash}SPI1_MISO{slash}TIM1_BKIN{slash}TIM3_CH1{slash}TIM8_BKIN{slash}TIM13_CH1{slash}DCMI_PIXCLK{slash}ADC12_IN6-Pad42)") (class "Default")
      (node (ref "U1") (pin "42") (pinfunction "PA6/SPI1_MISO/TIM1_BKIN/TIM3_CH1/TIM8_BKIN/TIM13_CH1/DCMI_PIXCLK/ADC12_IN6_42") (pintype "passive"))
    )
    (net (code "65") (name "unconnected-(U1-PA8{slash}TIM1_CH1{slash}U1_CK{slash}I2C3_SCL{slash}MCO1{slash}OTG_FS_SOF-Pad100)") (class "Default")
      (node (ref "U1") (pin "100") (pinfunction "PA8/TIM1_CH1/U1_CK/I2C3_SCL/MCO1/OTG_FS_SOF_100") (pintype "passive"))
    )
    (net (code "66") (name "unconnected-(U1-PA11{slash}TIM1_CH4{slash}U1_CTS{slash}CAN1_RX{slash}OTG_FS_DM-Pad103)") (class "Default")
      (node (ref "U1") (pin "103") (pinfunction "PA11/TIM1_CH4/U1_CTS/CAN1_RX/OTG_FS_DM_103") (pintype "passive"))
    )
    (net (code "67") (name "unconnected-(U1-PA12{slash}TIM1_ETR{slash}U1_RTS{slash}CAN1_TX{slash}OTG_FS_DP-Pad104)") (class "Default")
      (node (ref "U1") (pin "104") (pinfunction "PA12/TIM1_ETR/U1_RTS/CAN1_TX/OTG_FS_DP_104") (pintype "passive"))
    )
    (net (code "68") (name "unconnected-(U1-PA15{slash}JTDI{slash}SPI1_NSS{slash}SPI3_NSS{slash}TIM2_CH1_ETR{slash}I2S3_WS-Pad110)") (class "Default")
      (node (ref "U1") (pin "110") (pinfunction "PA15/JTDI/SPI1_NSS/SPI3_NSS/TIM2_CH1_ETR/I2S3_WS_110") (pintype "passive"))
    )
    (net (code "69") (name "unconnected-(U1-PB10{slash}SPI2_SCK{slash}TIM2_CH3{slash}U3_TX{slash}I2C2_SCL{slash}OTG_HS_ULPI_D3{slash}I2S2_CK-Pad69)") (class "Default")
      (node (ref "U1") (pin "69") (pinfunction "PB10/SPI2_SCK/TIM2_CH3/U3_TX/I2C2_SCL/OTG_HS_ULPI_D3/I2S2_CK_69") (pintype "passive"))
    )
    (net (code "70") (name "unconnected-(U1-PB11{slash}TIM2_CH4{slash}U3_RX{slash}I2C2_SDA{slash}HS_ULPI_D4{slash}ETH_MII_TX_EN{slash}ETH_RMII_TX_EN-Pad70)") (class "Default")
      (node (ref "U1") (pin "70") (pinfunction "PB11/TIM2_CH4/U3_RX/I2C2_SDA/HS_ULPI_D4/ETH_MII_TX_EN/ETH_RMII_TX_EN_70") (pintype "passive"))
    )
    (net (code "71") (name "unconnected-(U1-PB12{slash}SPI2_NSS{slash}TIM1_BKIN{slash}U3_CK{slash}CAN2_RX{slash}I2C2_SMBA{slash}OTG_HS_ULPI_D5{slash}OTG_HS_ID{slash}ETH_MII_TXD0{slash}ETH_RMII_TXD0{slash}I2S2_WS-Pad73)") (class "Default")
      (node (ref "U1") (pin "73") (pinfunction "PB12/SPI2_NSS/TIM1_BKIN/U3_CK/CAN2_RX/I2C2_SMBA/OTG_HS_ULPI_D5/OTG_HS_ID/ETH_MII_TXD0/ETH_RMII_TXD0/I2S2_WS_73") (pintype "passive"))
    )
    (net (code "72") (name "unconnected-(U1-PB13{slash}SPI2_SCK{slash}TIM1_CH1N{slash}U3_CTS{slash}CAN2_TX{slash}OTG_HS_ULPI_D6{slash}OTG_HS_VBUS{slash}ETH_MII_TXD1{slash}ETH_RMII_TXD1{slash}I2S2_CK-Pad74)") (class "Default")
      (node (ref "U1") (pin "74") (pinfunction "PB13/SPI2_SCK/TIM1_CH1N/U3_CTS/CAN2_TX/OTG_HS_ULPI_D6/OTG_HS_VBUS/ETH_MII_TXD1/ETH_RMII_TXD1/I2S2_CK_74") (pintype "passive"))
    )
    (net (code "73") (name "unconnected-(U1-PC2{slash}SPI2_MISO{slash}OTG_HS_ULPI_DIR{slash}ETH_MII_TXD2{slash}I2S2ext_SD{slash}ADC123_IN12-Pad28)") (class "Default")
      (node (ref "U1") (pin "28") (pinfunction "PC2/SPI2_MISO/OTG_HS_ULPI_DIR/ETH_MII_TXD2/I2S2ext_SD/ADC123_IN12_28") (pintype "passive"))
    )
    (net (code "74") (name "unconnected-(U1-PC3{slash}SPI2_MOSI{slash}OTG_HS_ULPI_NXT{slash}ETH_MII_TX_CLK{slash}I2S2_SD{slash}ADC123_IN13-Pad29)") (class "Default")
      (node (ref "U1") (pin "29") (pinfunction "PC3/SPI2_MOSI/OTG_HS_ULPI_NXT/ETH_MII_TX_CLK/I2S2_SD/ADC123_IN13_29") (pintype "passive"))
    )
    (net (code "75") (name "unconnected-(U1-PC4{slash}ETH_MII_RXD0{slash}ETH_RMII_RXD0{slash}ADC12_IN14-Pad44)") (class "Default")
      (node (ref "U1") (pin "44") (pinfunction "PC4/ETH_MII_RXD0/ETH_RMII_RXD0/ADC12_IN14_44") (pintype "passive"))
    )
    (net (code "76") (name "unconnected-(U1-PC5{slash}ETH_MII_RXD1{slash}ETH_RMII_RXD1{slash}ADC12_IN15-Pad45)") (class "Default")
      (node (ref "U1") (pin "45") (pinfunction "PC5/ETH_MII_RXD1/ETH_RMII_RXD1/ADC12_IN15_45") (pintype "passive"))
    )
    (net (code "77") (name "unconnected-(U1-PC9{slash}TIM3_CH4{slash}TIM8_CH4{slash}I2C3_SDA{slash}SDIO_D1{slash}DCMI_D3{slash}MCO2{slash}I2S_CKIN-Pad99)") (class "Default")
      (node (ref "U1") (pin "99") (pinfunction "PC9/TIM3_CH4/TIM8_CH4/I2C3_SDA/SDIO_D1/DCMI_D3/MCO2/I2S_CKIN_99") (pintype "passive"))
    )
    (net (code "78") (name "unconnected-(U1-PC10{slash}SPI3_SCK{slash}U3_TX{slash}U4_TX{slash}SDIO_D2{slash}DCMI_D8{slash}I2S3_CK-Pad111)") (class "Default")
      (node (ref "U1") (pin "111") (pinfunction "PC10/SPI3_SCK/U3_TX/U4_TX/SDIO_D2/DCMI_D8/I2S3_CK_111") (pintype "passive"))
    )
    (net (code "79") (name "unconnected-(U1-PC11{slash}SPI3_MISO{slash}U3_RX{slash}U4_RX{slash}SDIO_D3{slash}DCMI_D4{slash}I2S3ext_SD-Pad112)") (class "Default")
      (node (ref "U1") (pin "112") (pinfunction "PC11/SPI3_MISO/U3_RX/U4_RX/SDIO_D3/DCMI_D4/I2S3ext_SD_112") (pintype "passive"))
    )
    (net (code "80") (name "unconnected-(U1-PC12{slash}SPI3_MOSI{slash}U3_CK{slash}U5_TX{slash}SDIO_CK{slash}DCMI_D9{slash}I2S3_SD-Pad113)") (class "Default")
      (node (ref "U1") (pin "113") (pinfunction "PC12/SPI3_MOSI/U3_CK/U5_TX/SDIO_CK/DCMI_D9/I2S3_SD_113") (pintype "passive"))
    )
    (net (code "81") (name "unconnected-(U1-PC13{slash}RTC_AF1-Pad7)") (class "Default")
      (node (ref "U1") (pin "7") (pinfunction "PC13/RTC_AF1_7") (pintype "passive"))
    )
    (net (code "82") (name "unconnected-(U1-PC14-OSC32_IN-Pad8)") (class "Default")
      (node (ref "U1") (pin "8") (pinfunction "PC14-OSC32_IN_8") (pintype "passive"))
    )
    (net (code "83") (name "unconnected-(U1-PC15-OSC32_OUT-Pad9)") (class "Default")
      (node (ref "U1") (pin "9") (pinfunction "PC15-OSC32_OUT_9") (pintype "passive"))
    )
    (net (code "84") (name "unconnected-(U1-PD0{slash}FSMC_D2{slash}CAN1_RX-Pad114)") (class "Default")
      (node (ref "U1") (pin "114") (pinfunction "PD0/FSMC_D2/CAN1_RX_114") (pintype "passive"))
    )
    (net (code "85") (name "unconnected-(U1-PD1{slash}FSMC_D3{slash}CAN1_TX-Pad115)") (class "Default")
      (node (ref "U1") (pin "115") (pinfunction "PD1/FSMC_D3/CAN1_TX_115") (pintype "passive"))
    )
    (net (code "86") (name "unconnected-(U1-PD2{slash}TIM3_ETR{slash}U5_RX{slash}SDIO_CMD{slash}DCMI_D11-Pad116)") (class "Default")
      (node (ref "U1") (pin "116") (pinfunction "PD2/TIM3_ETR/U5_RX/SDIO_CMD/DCMI_D11_116") (pintype "passive"))
    )
    (net (code "87") (name "unconnected-(U1-PD3{slash}FSMC_CLK{slash}U2_CTS-Pad117)") (class "Default")
      (node (ref "U1") (pin "117") (pinfunction "PD3/FSMC_CLK/U2_CTS_117") (pintype "passive"))
    )
    (net (code "88") (name "unconnected-(U1-PD4{slash}FSMC_NOE{slash}U2_RTS-Pad118)") (class "Default")
      (node (ref "U1") (pin "118") (pinfunction "PD4/FSMC_NOE/U2_RTS_118") (pintype "passive"))
    )
    (net (code "89") (name "unconnected-(U1-PD5{slash}FSMC_NWE{slash}U2_TX-Pad119)") (class "Default")
      (node (ref "U1") (pin "119") (pinfunction "PD5/FSMC_NWE/U2_TX_119") (pintype "passive"))
    )
    (net (code "90") (name "unconnected-(U1-PD6{slash}FSMC_NWAIT{slash}U2_RX-Pad122)") (class "Default")
      (node (ref "U1") (pin "122") (pinfunction "PD6/FSMC_NWAIT/U2_RX_122") (pintype "passive"))
    )
    (net (code "91") (name "unconnected-(U1-PD7{slash}FSMC_NE1{slash}FSMC_NCE2{slash}U2_CK-Pad123)") (class "Default")
      (node (ref "U1") (pin "123") (pinfunction "PD7/FSMC_NE1/FSMC_NCE2/U2_CK_123") (pintype "passive"))
    )
    (net (code "92") (name "unconnected-(U1-PD8{slash}FSMC_D13{slash}U3_TX-Pad77)") (class "Default")
      (node (ref "U1") (pin "77") (pinfunction "PD8/FSMC_D13/U3_TX_77") (pintype "passive"))
    )
    (net (code "93") (name "unconnected-(U1-PD10{slash}FSMC_D15{slash}U3_CK-Pad79)") (class "Default")
      (node (ref "U1") (pin "79") (pinfunction "PD10/FSMC_D15/U3_CK_79") (pintype "passive"))
    )
    (net (code "94") (name "unconnected-(U1-PD12{slash}FSMC_A17{slash}FSMC_ALE{slash}TIM4_CH1{slash}U3_RTS-Pad81)") (class "Default")
      (node (ref "U1") (pin "81") (pinfunction "PD12/FSMC_A17/FSMC_ALE/TIM4_CH1/U3_RTS_81") (pintype "passive"))
    )
    (net (code "95") (name "unconnected-(U1-PD14{slash}FSMC_D0{slash}TIM4_CH3-Pad85)") (class "Default")
      (node (ref "U1") (pin "85") (pinfunction "PD14/FSMC_D0/TIM4_CH3_85") (pintype "passive"))
    )
    (net (code "96") (name "unconnected-(U1-PDR_ON-Pad143)") (class "Default")
      (node (ref "U1") (pin "143") (pinfunction "PDR_ON_143") (pintype "passive"))
    )
    (net (code "97") (name "unconnected-(U1-PE0{slash}TIM4_ETR{slash}FSMC_NBL0{slash}DCMI_D2-Pad141)") (class "Default")
      (node (ref "U1") (pin "141") (pinfunction "PE0/TIM4_ETR/FSMC_NBL0/DCMI_D2_141") (pintype "passive"))
    )
    (net (code "98") (name "unconnected-(U1-PE1{slash}FSMC_NBL1{slash}DCMI_D3-Pad142)") (class "Default")
      (node (ref "U1") (pin "142") (pinfunction "PE1/FSMC_NBL1/DCMI_D3_142") (pintype "passive"))
    )
    (net (code "99") (name "unconnected-(U1-PE2{slash}TRACECLK{slash}FSMC_A23{slash}ETH_MII_TXD3-Pad1)") (class "Default")
      (node (ref "U1") (pin "1") (pinfunction "PE2/TRACECLK/FSMC_A23/ETH_MII_TXD3_1") (pintype "passive"))
    )
    (net (code "100") (name "unconnected-(U1-PE3{slash}TRACED0{slash}FSMC_A19-Pad2)") (class "Default")
      (node (ref "U1") (pin "2") (pinfunction "PE3/TRACED0/FSMC_A19_2") (pintype "passive"))
    )
    (net (code "101") (name "unconnected-(U1-PE4{slash}TRACED1{slash}FSMC_A20{slash}DCMI_D4-Pad3)") (class "Default")
      (node (ref "U1") (pin "3") (pinfunction "PE4/TRACED1/FSMC_A20/DCMI_D4_3") (pintype "passive"))
    )
    (net (code "102") (name "unconnected-(U1-PE5{slash}TRACED2{slash}FSMC_A21{slash}TIM9_CH1{slash}DCMI_D6-Pad4)") (class "Default")
      (node (ref "U1") (pin "4") (pinfunction "PE5/TRACED2/FSMC_A21/TIM9_CH1/DCMI_D6_4") (pintype "passive"))
    )
    (net (code "103") (name "unconnected-(U1-PE6{slash}TRACED3{slash}FSMC_A22{slash}TIM9_CH2{slash}DCMI_D7-Pad5)") (class "Default")
      (node (ref "U1") (pin "5") (pinfunction "PE6/TRACED3/FSMC_A22/TIM9_CH2/DCMI_D7_5") (pintype "passive"))
    )
    (net (code "104") (name "unconnected-(U1-PE7{slash}FSMC_D4{slash}TIM1_ETR-Pad58)") (class "Default")
      (node (ref "U1") (pin "58") (pinfunction "PE7/FSMC_D4/TIM1_ETR_58") (pintype "passive"))
    )
    (net (code "105") (name "unconnected-(U1-PE12{slash}FSMC_D9{slash}TIM1_CH3N-Pad65)") (class "Default")
      (node (ref "U1") (pin "65") (pinfunction "PE12/FSMC_D9/TIM1_CH3N_65") (pintype "passive"))
    )
    (net (code "106") (name "unconnected-(U1-PE13{slash}FSMC_D10{slash}TIM1_CH3-Pad66)") (class "Default")
      (node (ref "U1") (pin "66") (pinfunction "PE13/FSMC_D10/TIM1_CH3_66") (pintype "passive"))
    )
    (net (code "107") (name "unconnected-(U1-PE14{slash}FSMC_D11{slash}TIM1_CH4-Pad67)") (class "Default")
      (node (ref "U1") (pin "67") (pinfunction "PE14/FSMC_D11/TIM1_CH4_67") (pintype "passive"))
    )
    (net (code "108") (name "unconnected-(U1-PE15{slash}FSMC_D12{slash}TIM1_BKIN-Pad68)") (class "Default")
      (node (ref "U1") (pin "68") (pinfunction "PE15/FSMC_D12/TIM1_BKIN_68") (pintype "passive"))
    )
    (net (code "109") (name "unconnected-(U1-PF3{slash}FSMC_A3{slash}ADC3_IN9-Pad13)") (class "Default")
      (node (ref "U1") (pin "13") (pinfunction "PF3/FSMC_A3/ADC3_IN9_13") (pintype "passive"))
    )
    (net (code "110") (name "unconnected-(U1-PF4{slash}FSMC_A4{slash}ADC3_IN14-Pad14)") (class "Default")
      (node (ref "U1") (pin "14") (pinfunction "PF4/FSMC_A4/ADC3_IN14_14") (pintype "passive"))
    )
    (net (code "111") (name "unconnected-(U1-PF5{slash}FSMC_A5{slash}ADC3_IN15-Pad15)") (class "Default")
      (node (ref "U1") (pin "15") (pinfunction "PF5/FSMC_A5/ADC3_IN15_15") (pintype "passive"))
    )
    (net (code "112") (name "unconnected-(U1-PF6{slash}TIM10_CH1{slash}FSMC_NIORD{slash}ADC3_IN4-Pad18)") (class "Default")
      (node (ref "U1") (pin "18") (pinfunction "PF6/TIM10_CH1/FSMC_NIORD/ADC3_IN4_18") (pintype "passive"))
    )
    (net (code "113") (name "unconnected-(U1-PF7{slash}TIM11_CH1{slash}FSMC_NREG{slash}ADC3_IN5-Pad19)") (class "Default")
      (node (ref "U1") (pin "19") (pinfunction "PF7/TIM11_CH1/FSMC_NREG/ADC3_IN5_19") (pintype "passive"))
    )
    (net (code "114") (name "unconnected-(U1-PF8{slash}TIM13_CH1{slash}FSMC_NIOWR{slash}ADC3_IN6-Pad20)") (class "Default")
      (node (ref "U1") (pin "20") (pinfunction "PF8/TIM13_CH1/FSMC_NIOWR/ADC3_IN6_20") (pintype "passive"))
    )
    (net (code "115") (name "unconnected-(U1-PF9{slash}TIM14_CH1{slash}FSMC_CD{slash}ADC3_IN7-Pad21)") (class "Default")
      (node (ref "U1") (pin "21") (pinfunction "PF9/TIM14_CH1/FSMC_CD/ADC3_IN7_21") (pintype "passive"))
    )
    (net (code "116") (name "unconnected-(U1-PF10{slash}FSMC_INTR{slash}ADC3_IN8-Pad22)") (class "Default")
      (node (ref "U1") (pin "22") (pinfunction "PF10/FSMC_INTR/ADC3_IN8_22") (pintype "passive"))
    )
    (net (code "117") (name "unconnected-(U1-PF11{slash}DCMI_D12-Pad49)") (class "Default")
      (node (ref "U1") (pin "49") (pinfunction "PF11/DCMI_D12_49") (pintype "passive"))
    )
    (net (code "118") (name "unconnected-(U1-PF12{slash}FSMC_A6-Pad50)") (class "Default")
      (node (ref "U1") (pin "50") (pinfunction "PF12/FSMC_A6_50") (pintype "passive"))
    )
    (net (code "119") (name "unconnected-(U1-PF13{slash}FSMC_A7-Pad53)") (class "Default")
      (node (ref "U1") (pin "53") (pinfunction "PF13/FSMC_A7_53") (pintype "passive"))
    )
    (net (code "120") (name "unconnected-(U1-PF14{slash}FSMC_A8-Pad54)") (class "Default")
      (node (ref "U1") (pin "54") (pinfunction "PF14/FSMC_A8_54") (pintype "passive"))
    )
    (net (code "121") (name "unconnected-(U1-PF15{slash}FSMC_A9-Pad55)") (class "Default")
      (node (ref "U1") (pin "55") (pinfunction "PF15/FSMC_A9_55") (pintype "passive"))
    )
    (net (code "122") (name "unconnected-(U1-PG0{slash}FSMC_A10-Pad56)") (class "Default")
      (node (ref "U1") (pin "56") (pinfunction "PG0/FSMC_A10_56") (pintype "passive"))
    )
    (net (code "123") (name "unconnected-(U1-PG1{slash}FSMC_A11-Pad57)") (class "Default")
      (node (ref "U1") (pin "57") (pinfunction "PG1/FSMC_A11_57") (pintype "passive"))
    )
    (net (code "124") (name "unconnected-(U1-PG2{slash}FSMC_A12-Pad87)") (class "Default")
      (node (ref "U1") (pin "87") (pinfunction "PG2/FSMC_A12_87") (pintype "passive"))
    )
    (net (code "125") (name "unconnected-(U1-PG3{slash}FSMC_A13-Pad88)") (class "Default")
      (node (ref "U1") (pin "88") (pinfunction "PG3/FSMC_A13_88") (pintype "passive"))
    )
    (net (code "126") (name "unconnected-(U1-PG4{slash}FSMC_A14-Pad89)") (class "Default")
      (node (ref "U1") (pin "89") (pinfunction "PG4/FSMC_A14_89") (pintype "passive"))
    )
    (net (code "127") (name "unconnected-(U1-PG5{slash}FSMC_A15-Pad90)") (class "Default")
      (node (ref "U1") (pin "90") (pinfunction "PG5/FSMC_A15_90") (pintype "passive"))
    )
    (net (code "128") (name "unconnected-(U1-PG6{slash}FSMC_INT2-Pad91)") (class "Default")
      (node (ref "U1") (pin "91") (pinfunction "PG6/FSMC_INT2_91") (pintype "passive"))
    )
    (net (code "129") (name "unconnected-(U1-PG7{slash}FSMC_INT3{slash}U6_CK-Pad92)") (class "Default")
      (node (ref "U1") (pin "92") (pinfunction "PG7/FSMC_INT3/U6_CK_92") (pintype "passive"))
    )
    (net (code "130") (name "unconnected-(U1-PG8{slash}U6_RTS{slash}ETH_PPS_OUT-Pad93)") (class "Default")
      (node (ref "U1") (pin "93") (pinfunction "PG8/U6_RTS/ETH_PPS_OUT_93") (pintype "passive"))
    )
    (net (code "131") (name "unconnected-(U1-PG9{slash}FSMC_NE2{slash}FSMC_NCE3{slash}U6_RX-Pad124)") (class "Default")
      (node (ref "U1") (pin "124") (pinfunction "PG9/FSMC_NE2/FSMC_NCE3/U6_RX_124") (pintype "passive"))
    )
    (net (code "132") (name "unconnected-(U1-PG10{slash}FSMC_NCE4_1{slash}FSMC_NE3-Pad125)") (class "Default")
      (node (ref "U1") (pin "125") (pinfunction "PG10/FSMC_NCE4_1/FSMC_NE3_125") (pintype "passive"))
    )
    (net (code "133") (name "unconnected-(U1-PG11{slash}FSMC_NCE4_2{slash}ETH_MII_TX_EN{slash}ETH_RMII_TX_EN-Pad126)") (class "Default")
      (node (ref "U1") (pin "126") (pinfunction "PG11/FSMC_NCE4_2/ETH_MII_TX_EN/ETH_RMII_TX_EN_126") (pintype "passive"))
    )
    (net (code "134") (name "unconnected-(U1-PG12{slash}FSMC_NE4{slash}U6_RTS-Pad127)") (class "Default")
      (node (ref "U1") (pin "127") (pinfunction "PG12/FSMC_NE4/U6_RTS_127") (pintype "passive"))
    )
    (net (code "135") (name "unconnected-(U1-PG13{slash}FSMC_A24{slash}U6_CTS{slash}ETH_MII_TXD0{slash}ETH_RMII_TXD0-Pad128)") (class "Default")
      (node (ref "U1") (pin "128") (pinfunction "PG13/FSMC_A24/U6_CTS/ETH_MII_TXD0/ETH_RMII_TXD0_128") (pintype "passive"))
    )
    (net (code "136") (name "unconnected-(U1-PG14{slash}FSMC_A25{slash}U6_TX{slash}ETH_MII_TXD1{slash}ETH_RMII_TXD1-Pad129)") (class "Default")
      (node (ref "U1") (pin "129") (pinfunction "PG14/FSMC_A25/U6_TX/ETH_MII_TXD1/ETH_RMII_TXD1_129") (pintype "passive"))
    )
    (net (code "137") (name "unconnected-(U1-PG15{slash}U6_CTS{slash}DCMI_D13-Pad132)") (class "Default")
      (node (ref "U1") (pin "132") (pinfunction "PG15/U6_CTS/DCMI_D13_132") (pintype "passive"))
    )
    (net (code "138") (name "unconnected-(U3-DNC-Pad1)") (class "Default")
      (node (ref "U3") (pin "1") (pinfunction "DNC_1") (pintype "passive"))
    )
    (net (code "139") (name "unconnected-(U3-DNC-Pad8)") (class "Default")
      (node (ref "U3") (pin "8") (pinfunction "DNC_8") (pintype "passive"))
    )
    (net (code "140") (name "unconnected-(U3-NC-Pad7)") (class "Default")
      (node (ref "U3") (pin "7") (pinfunction "NC_7") (pintype "passive"))
    )
    (net (code "141") (name "unconnected-(U3-TEMP-Pad3)") (class "Default")
      (node (ref "U3") (pin "3") (pinfunction "TEMP_3") (pintype "passive"))
    )
    (net (code "142") (name "unconnected-(USB1-D+-Pad3)") (class "Default")
      (node (ref "USB1") (pin "3") (pinfunction "D+_3") (pintype "passive"))
    )
    (net (code "143") (name "unconnected-(USB1-D--Pad2)") (class "Default")
      (node (ref "USB1") (pin "2") (pinfunction "D-_2") (pintype "passive"))
    )
    (net (code "144") (name "unconnected-(USB1-ID-Pad4)") (class "Default")
      (node (ref "USB1") (pin "4") (pinfunction "ID_4") (pintype "passive"))
    )
  )
)
